# Module_PS6W_24233_ISO.net
KiCad netlist of a schematic drawn in Altium Designer
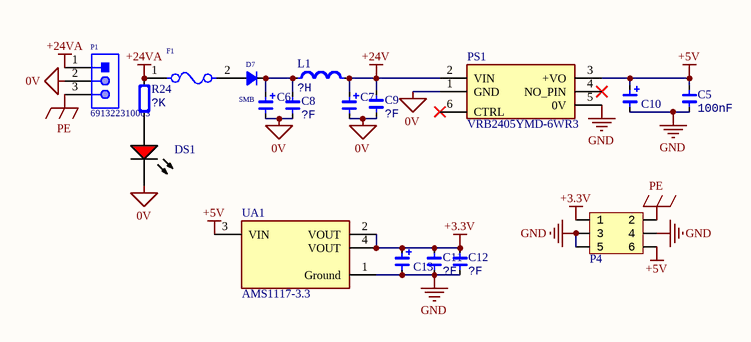
[diagram p0: [Module]PS6W_24233_ISO.SchDoc]

(export (version "E")
  (design (tool "Eeschema 10.0.6"))
  (components
    (comp (ref "C5")
      (value "100nF")
      (footprint "CAP-0805")
      (description "Capacitor")
      (fields (field (name "Comment") "Cap_0805"))
      (libsource (lib "") (part "Cap_0805_1"))
    )
    (comp (ref "C6")
      (value "Cap_Alu_8.3mm")
      (footprint "CAP ALUM 8.3MM")
      (description "Capacitor Alunium")
      (libsource (lib "Integrated_Library") (part "Cap_Alu_8.3mm"))
    )
    (comp (ref "C7")
      (value "Cap_Alu_8.3mm")
      (footprint "CAP ALUM 8.3MM")
      (description "Capacitor Alunium")
      (libsource (lib "Integrated_Library") (part "Cap_Alu_8.3mm"))
    )
    (comp (ref "C8")
      (value "?F")
      (footprint "CAP-0805")
      (description "Capacitor")
      (fields (field (name "Comment") "Cap_0805"))
      (libsource (lib "") (part "Cap_0805_1"))
    )
    (comp (ref "C9")
      (value "?F")
      (footprint "CAP-0805")
      (description "Capacitor")
      (fields (field (name "Comment") "Cap_0805"))
      (libsource (lib "") (part "Cap_0805_1"))
    )
    (comp (ref "C10")
      (value "Cap_Alu_6.6mm")
      (footprint "CAP ALUM 6.6MM")
      (description "Capacitor Alunium")
      (libsource (lib "Integrated_Library") (part "Cap_Alu_6.6mm"))
    )
    (comp (ref "C11")
      (value "?F")
      (footprint "CAP-0805")
      (description "Capacitor")
      (fields (field (name "Comment") "Cap_0805"))
      (libsource (lib "Integrated_Library") (part "Cap_0805"))
    )
    (comp (ref "C12")
      (value "?F")
      (footprint "CAP-0805")
      (description "Capacitor")
      (fields (field (name "Comment") "Cap_0805"))
      (libsource (lib "Integrated_Library") (part "Cap_0805"))
    )
    (comp (ref "C13")
      (value "Cap_Alu_6.6mm")
      (footprint "CAP ALUM 6.6MM")
      (description "Capacitor Alunium")
      (libsource (lib "Integrated_Library") (part "Cap_Alu_6.6mm"))
    )
    (comp (ref "D7")
      (value "NAME")
      (footprint "DO-214AA")
      (description "Diode")
      (fields (field (name "TYPE") "SMB"))
      (libsource (lib "Integrated_Library") (part "Diode_SMB"))
    )
    (comp (ref "DS1")
      (value "C503B-RAN-CY0B0AA2")
      (footprint "CREE-C503B-RAN")
      (description "Cree(R) 5-mm Red Round LED, 2.1 V, -40 to 100 degC, 2-Pin THD, RoHS, Ammo")
      (fields (field (name "MANUFACTURER") "Cree"))
      (libsource (lib "Altium Content Vault") (part "LED-RED-AK-2"))
    )
    (comp (ref "F1")
      (value "0451005.MRL")
      (footprint "FP-0451-MFG")
      (description "FUSE BRD MNT 5A 125VAC/VDC 2SMD")
      (fields
        (field (name "OCTOPART") "https://octopart.com/0451005.mrl-littelfuse-566389")
        (field (name "MANUFACTURER") "Littelfuse Inc")
      )
      (libsource (lib "Altium Content Vault") (part "5bcf9b9f640e542cf0359d10258e979"))
    )
    (comp (ref "L1")
      (value "?H")
      (footprint "INDP120120X80N")
      (description "SMD Inductor")
      (fields (field (name "Comment") "Inductor"))
      (libsource (lib "Integrated_Library") (part "Inductor"))
    )
    (comp (ref "P1")
      (value "691322310003")
      (footprint "691322310003")
      (description "Serie 322 - 3.81mm Horizontal PCB Header WR-TBL, 3 pin")
      (fields (field (name "MANUFACTURER") "Wurth Elektronik") (field (name "PUBLISHER") "WurthElektronik"))
      (libsource (lib "Altium Content Vault") (part "WE-CN-1P-M-R3"))
    )
    (comp (ref "P4")
      (value "HDR2x3")
      (footprint "HDR2X3_2.54_180")
      (description "Header")
      (libsource (lib "Integrated_Library") (part "HDR2x3_2.54"))
    )
    (comp (ref "PS1")
      (value "VRB2405YMD-6WR3")
      (footprint "VRB2405YMD6WR3")
      (description "Power Supply")
      (libsource (lib "Integrated_Library") (part "VRB2405YMD-6WR3"))
    )
    (comp (ref "R24")
      (value "?K")
      (footprint "RES-1206")
      (description "Resistor")
      (fields (field (name "Comment") "Res_1206"))
      (libsource (lib "Integrated_Library") (part "Res_1206"))
    )
    (comp (ref "UA1")
      (value "AMS1117-3.3")
      (footprint "FP-AMS1117-IPC_C")
      (description "LDO Voltage Regulators 1A, 3.3V")
      (fields
        (field (name "OCTOPART") "https://octopart.com/ams1117-3.3-advanced+monolithic+systems-25899300")
        (field (name "MANUFACTURER") "Advanced Monolithic Systems")
      )
      (libsource (lib "Altium Content Vault") (part "8bdbb5f8e77002000e30dd2845d0354"))
    )
  )
  (nets
    (net (code "1") (name "+3.3V") (class "Default")
      (node (ref "C11") (pin "1") (pinfunction "1_1") (pintype "passive"))
      (node (ref "C12") (pin "1") (pinfunction "1_1") (pintype "passive"))
      (node (ref "C13") (pin "1") (pinfunction "1_1") (pintype "passive"))
      (node (ref "P4") (pin "1") (pinfunction "1_1") (pintype "passive"))
      (node (ref "UA1") (pin "2") (pinfunction "VOUT_2") (pintype "passive"))
      (node (ref "UA1") (pin "4") (pinfunction "VOUT_4") (pintype "passive"))
    )
    (net (code "2") (name "+5V") (class "Default")
      (node (ref "C10") (pin "1") (pinfunction "1_1") (pintype "passive"))
      (node (ref "C5") (pin "2") (pinfunction "2_2") (pintype "passive"))
      (node (ref "P4") (pin "6") (pinfunction "6_6") (pintype "passive"))
      (node (ref "PS1") (pin "3") (pinfunction "+VO_3") (pintype "passive"))
      (node (ref "UA1") (pin "3") (pinfunction "VIN_3") (pintype "power_in"))
    )
    (net (code "3") (name "+24V") (class "Default")
      (node (ref "C7") (pin "1") (pinfunction "1_1") (pintype "passive"))
      (node (ref "C9") (pin "2") (pinfunction "2_2") (pintype "passive"))
      (node (ref "L1") (pin "2") (pinfunction "2_2") (pintype "passive"))
      (node (ref "PS1") (pin "2") (pinfunction "VIN_2") (pintype "passive"))
    )
    (net (code "4") (name "+24VA") (class "Default")
      (node (ref "F1") (pin "1") (pinfunction "1_1") (pintype "passive"))
      (node (ref "P1") (pin "1") (pinfunction "1_1") (pintype "passive"))
      (node (ref "R24") (pin "2") (pinfunction "2_2") (pintype "passive"))
    )
    (net (code "5") (name "0V") (class "Default")
      (node (ref "C6") (pin "2") (pinfunction "2_2") (pintype "passive"))
      (node (ref "C7") (pin "2") (pinfunction "2_2") (pintype "passive"))
      (node (ref "C8") (pin "1") (pinfunction "1_1") (pintype "passive"))
      (node (ref "C9") (pin "1") (pinfunction "1_1") (pintype "passive"))
      (node (ref "DS1") (pin "2") (pinfunction "K_2") (pintype "passive"))
      (node (ref "P1") (pin "2") (pinfunction "2_2") (pintype "passive"))
      (node (ref "PS1") (pin "1") (pinfunction "GND_1") (pintype "passive"))
    )
    (net (code "6") (name "GND") (class "Default")
      (node (ref "C10") (pin "2") (pinfunction "2_2") (pintype "passive"))
      (node (ref "C11") (pin "2") (pinfunction "2_2") (pintype "passive"))
      (node (ref "C12") (pin "2") (pinfunction "2_2") (pintype "passive"))
      (node (ref "C13") (pin "2") (pinfunction "2_2") (pintype "passive"))
      (node (ref "C5") (pin "1") (pinfunction "1_1") (pintype "passive"))
      (node (ref "P4") (pin "3") (pinfunction "3_3") (pintype "passive"))
      (node (ref "P4") (pin "4") (pinfunction "4_4") (pintype "passive"))
      (node (ref "P4") (pin "5") (pinfunction "5_5") (pintype "passive"))
      (node (ref "PS1") (pin "5") (pinfunction "0V_5") (pintype "passive"))
      (node (ref "UA1") (pin "1") (pinfunction "Ground_1") (pintype "power_in"))
    )
    (net (code "7") (name "Net-(D7-A)") (class "Default")
      (node (ref "D7") (pin "1") (pinfunction "A_1") (pintype "passive"))
      (node (ref "F1") (pin "2") (pinfunction "2_2") (pintype "passive"))
    )
    (net (code "8") (name "Net-(D7-K)") (class "Default")
      (node (ref "C6") (pin "1") (pinfunction "1_1") (pintype "passive"))
      (node (ref "C8") (pin "2") (pinfunction "2_2") (pintype "passive"))
      (node (ref "D7") (pin "2") (pinfunction "K_2") (pintype "passive"))
      (node (ref "L1") (pin "1") (pinfunction "1_1") (pintype "passive"))
    )
    (net (code "9") (name "Net-(DS1-A)") (class "Default")
      (node (ref "DS1") (pin "1") (pinfunction "A_1") (pintype "passive"))
      (node (ref "R24") (pin "1") (pinfunction "1_1") (pintype "passive"))
    )
    (net (code "10") (name "PE") (class "Default")
      (node (ref "P1") (pin "3") (pinfunction "3_3") (pintype "passive"))
      (node (ref "P4") (pin "2") (pinfunction "2_2") (pintype "passive"))
    )
    (net (code "11") (name "unconnected-(PS1-CTRL-Pad6)") (class "Default")
      (node (ref "PS1") (pin "6") (pinfunction "CTRL_6") (pintype "passive+no_connect"))
    )
    (net (code "12") (name "unconnected-(PS1-NO_PIN-Pad4)") (class "Default")
      (node (ref "PS1") (pin "4") (pinfunction "NO_PIN_4") (pintype "passive+no_connect"))
    )
  )
)
